# top.net
KiCad netlist of a schematic drawn in Altium Designer
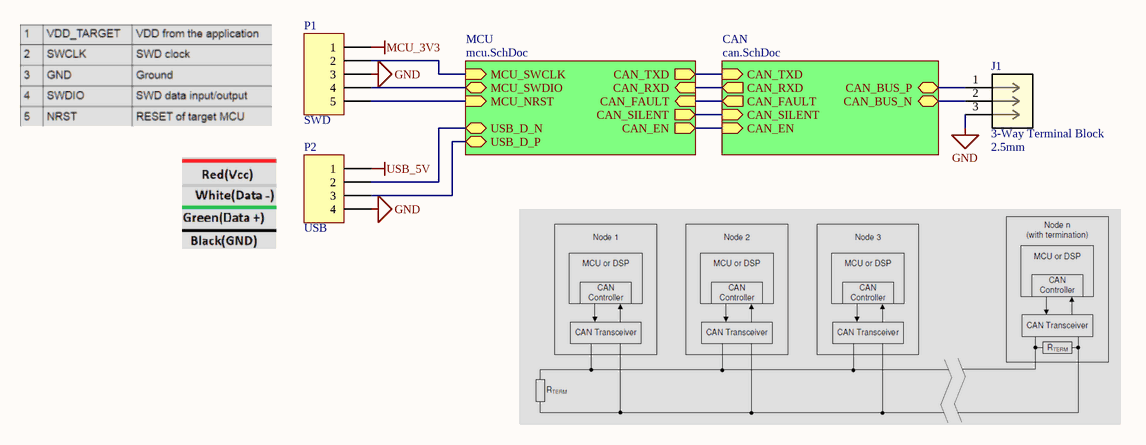
[diagram p0: top.SchDoc]

(export (version "E")
  (design (tool "Eeschema 10.0.6"))
  (components
    (comp (ref "J1")
      (value "3-Way Terminal Block")
      (footprint "TERMINAL_BLOCK_2.5MM_3WAY")
      (description "3-way wire to board terminal block")
      (fields (field (name "ALTIUM_VALUE") "2.5mm"))
      (libsource (lib "terminal_blocks") (part "3-Way Terminal Block"))
    )
    (comp (ref "P1")
      (value "Pin Header 5")
      (footprint "PIN_HEADER_1X5")
      (description "pin header, 5-pin")
      (libsource (lib "pin_headers") (part "Pin Header 5"))
    )
    (comp (ref "P2")
      (value "Pin Header 4")
      (footprint "PIN_HEADER_1X4")
      (description "pin header, 4-pin")
      (libsource (lib "pin_headers") (part "Pin Header 4"))
    )
  )
  (nets
    (net (code "1") (name "/CAN_BUS_N") (class "Default")
      (node (ref "J1") (pin "2") (pinfunction "2_2") (pintype "passive"))
    )
    (net (code "2") (name "/CAN_BUS_P") (class "Default")
      (node (ref "J1") (pin "1") (pinfunction "1_1") (pintype "passive"))
    )
    (net (code "8") (name "/MCU_NRST") (class "Default")
      (node (ref "P1") (pin "5") (pinfunction "5_5") (pintype "passive"))
    )
    (net (code "9") (name "/MCU_SWCLK") (class "Default")
      (node (ref "P1") (pin "2") (pinfunction "2_2") (pintype "passive"))
    )
    (net (code "10") (name "/MCU_SWDIO") (class "Default")
      (node (ref "P1") (pin "4") (pinfunction "4_4") (pintype "passive"))
    )
    (net (code "11") (name "/USB_D_N") (class "Default")
      (node (ref "P2") (pin "2") (pinfunction "2_2") (pintype "passive"))
    )
    (net (code "12") (name "/USB_D_P") (class "Default")
      (node (ref "P2") (pin "3") (pinfunction "3_3") (pintype "passive"))
    )
    (net (code "13") (name "GND") (class "Default")
      (node (ref "J1") (pin "3") (pinfunction "3_3") (pintype "passive"))
      (node (ref "P1") (pin "3") (pinfunction "3_3") (pintype "passive"))
      (node (ref "P2") (pin "4") (pinfunction "4_4") (pintype "passive"))
    )
    (net (code "14") (name "MCU_3V3") (class "Default")
      (node (ref "P1") (pin "1") (pinfunction "1_1") (pintype "passive"))
    )
    (net (code "15") (name "USB_5V") (class "Default")
      (node (ref "P2") (pin "1") (pinfunction "1_1") (pintype "passive"))
    )
  )
)
